# hub-i-proto-wireant01.net
KiCad netlist of a schematic drawn in EAGLE
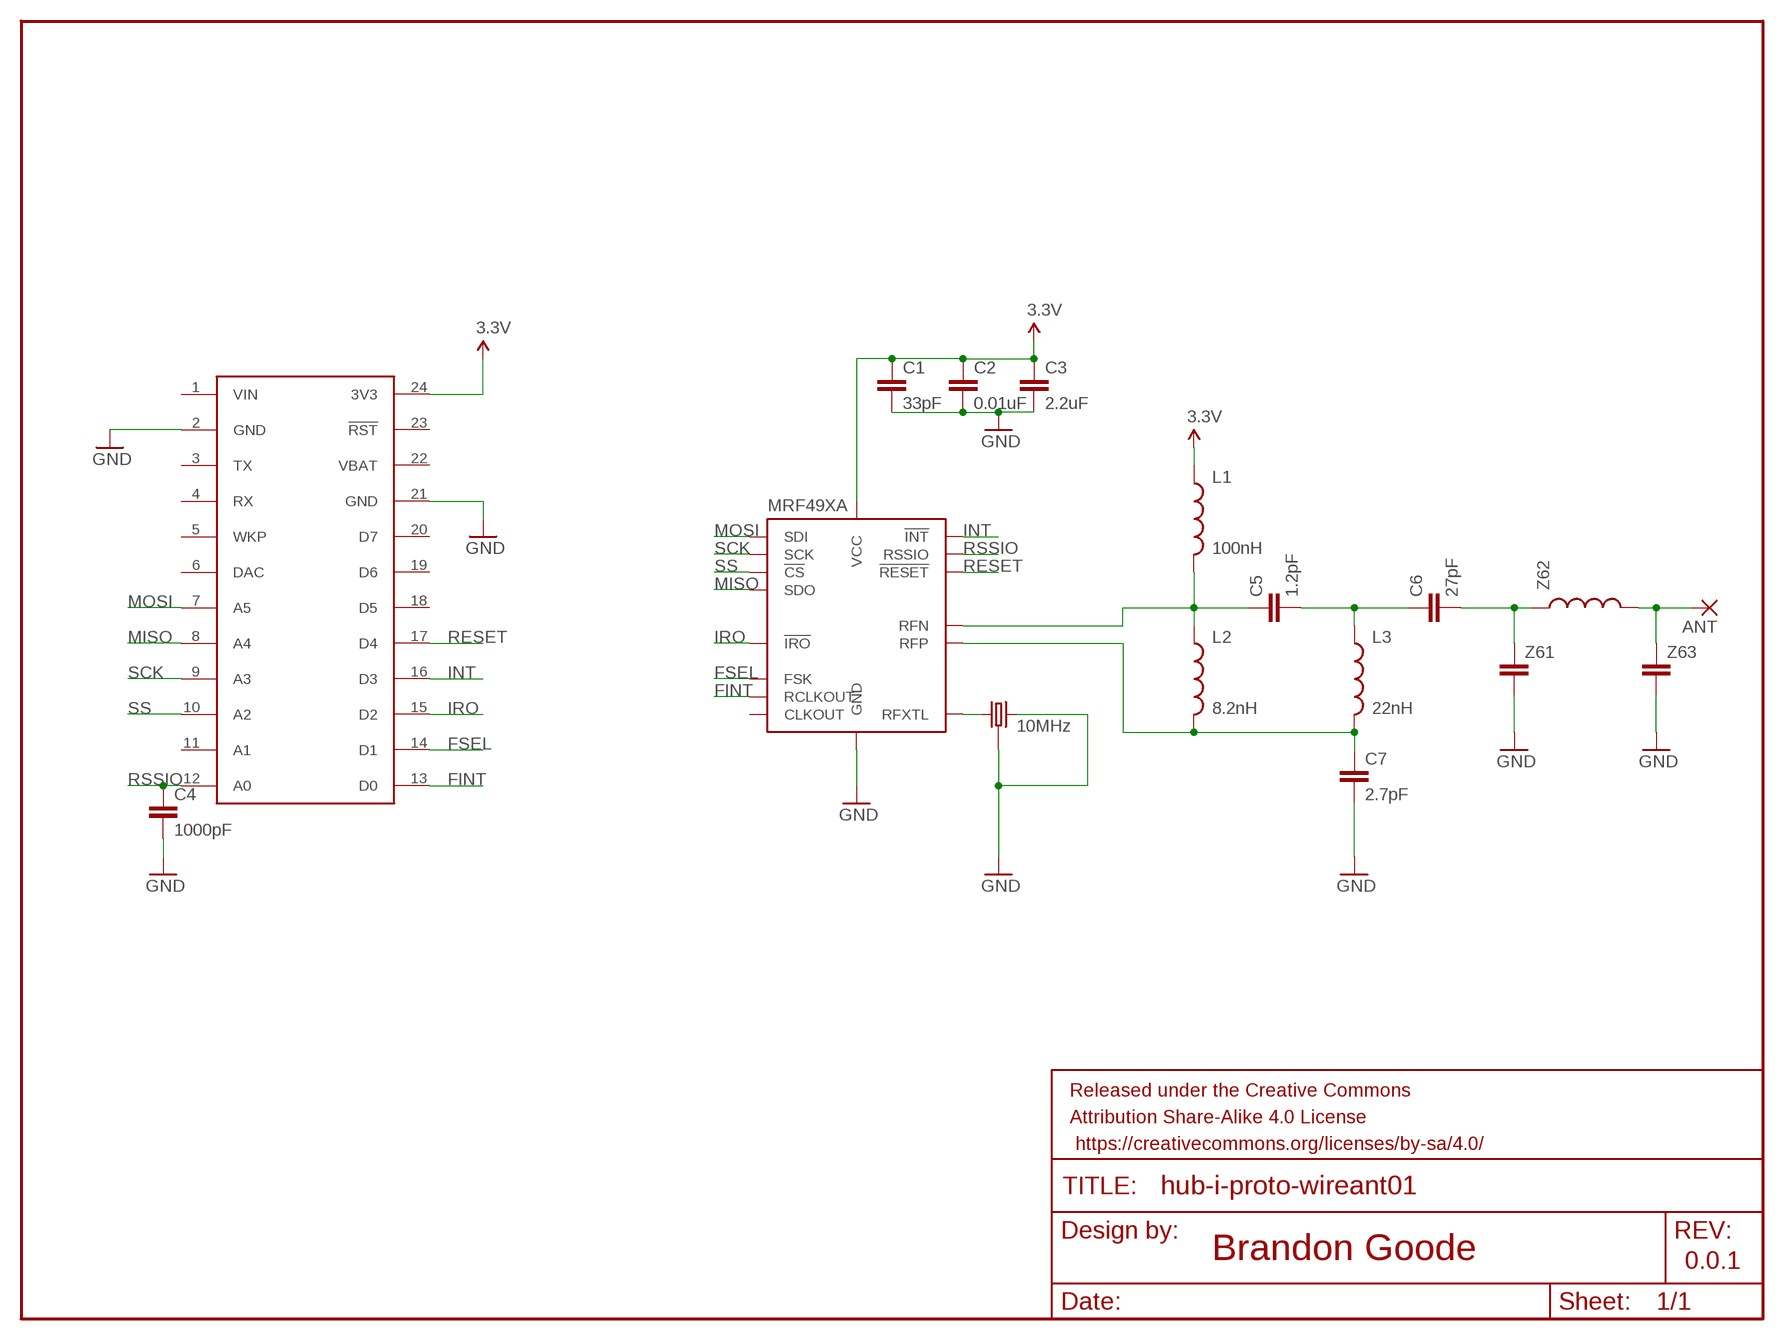
[diagram p0: schematic, sheet 1]

(export (version "E")
  (design (tool "Eeschema 10.0.6"))
  (components
    (comp (ref "ANT")
      (value "WIREPAD1,6/0,8")
      (footprint "eagle-import:1,6_0,8")
      (libsource (lib "eagle-import") (part "WIREPAD1,6/0,8"))
    )
    (comp (ref "C1")
      (value "33pF")
      (footprint "eagle-import:0603-CAP")
      (libsource (lib "eagle-import") (part "CAP0603-CAP"))
    )
    (comp (ref "C2")
      (value "0.01uF")
      (footprint "eagle-import:0603-CAP")
      (libsource (lib "eagle-import") (part "CAP0603-CAP"))
    )
    (comp (ref "C3")
      (value "2.2uF")
      (footprint "eagle-import:0603-CAP")
      (libsource (lib "eagle-import") (part "CAP0603-CAP"))
    )
    (comp (ref "C4")
      (value "1000pF")
      (footprint "eagle-import:0603-CAP")
      (libsource (lib "eagle-import") (part "CAP0603-CAP"))
    )
    (comp (ref "C5")
      (value "1.2pF")
      (footprint "eagle-import:0603-CAP")
      (libsource (lib "eagle-import") (part "CAP0603-CAP"))
    )
    (comp (ref "C6")
      (value "27pF")
      (footprint "eagle-import:0603-CAP")
      (libsource (lib "eagle-import") (part "CAP0603-CAP"))
    )
    (comp (ref "C7")
      (value "2.7pF")
      (footprint "eagle-import:0603-CAP")
      (libsource (lib "eagle-import") (part "CAP0603-CAP"))
    )
    (comp (ref "FRAME1")
      (value "FRAME-LETTER")
      (footprint "eagle-import:CREATIVE_COMMONS")
      (libsource (lib "eagle-import") (part "FRAME-LETTER"))
    )
    (comp (ref "L1")
      (value "100nH")
      (footprint "eagle-import:0603")
      (libsource (lib "eagle-import") (part "INDUCTOR0603"))
    )
    (comp (ref "L2")
      (value "8.2nH")
      (footprint "eagle-import:0603")
      (libsource (lib "eagle-import") (part "INDUCTOR0603"))
    )
    (comp (ref "L3")
      (value "22nH")
      (footprint "eagle-import:0603")
      (libsource (lib "eagle-import") (part "INDUCTOR0603"))
    )
    (comp (ref "MRF49XA")
      (value "MRF49XATSSOP")
      (footprint "eagle-import:TSSOP16")
      (libsource (lib "eagle-import") (part "MRF49XATSSOP"))
    )
    (comp (ref "SPARK")
      (value "SPARK_CORECORE")
      (footprint "eagle-import:SPARK_CORE")
      (libsource (lib "eagle-import") (part "SPARK_CORECORE"))
    )
    (comp (ref "Y1")
      (value "10MHz")
      (footprint "eagle-import:CRYSTAL-SMD-5X3")
      (libsource (lib "eagle-import") (part "CRYSTAL-GROUNDED"))
    )
    (comp (ref "Z61")
      (value "CAP0603-CAP")
      (footprint "eagle-import:0603-CAP")
      (libsource (lib "eagle-import") (part "CAP0603-CAP"))
    )
    (comp (ref "Z62")
      (value "INDUCTOR0603")
      (footprint "eagle-import:0603")
      (libsource (lib "eagle-import") (part "INDUCTOR0603"))
    )
    (comp (ref "Z63")
      (value "CAP0603-CAP")
      (footprint "eagle-import:0603-CAP")
      (libsource (lib "eagle-import") (part "CAP0603-CAP"))
    )
  )
  (nets
    (net (code "1") (name "/FINT") (class "Default")
      (node (ref "MRF49XA") (pin "7") (pinfunction "RCLKOUT_7") (pintype "bidirectional"))
      (node (ref "SPARK") (pin "13") (pinfunction "D0_13") (pintype "bidirectional"))
    )
    (net (code "2") (name "/FSEL") (class "Default")
      (node (ref "MRF49XA") (pin "6") (pinfunction "FSK_6") (pintype "bidirectional"))
      (node (ref "SPARK") (pin "14") (pinfunction "D1_14") (pintype "bidirectional"))
    )
    (net (code "3") (name "/INT") (class "Default")
      (node (ref "MRF49XA") (pin "16") (pinfunction "~{INT}_16") (pintype "bidirectional"))
      (node (ref "SPARK") (pin "16") (pinfunction "D3_16") (pintype "bidirectional"))
    )
    (net (code "4") (name "/IRO") (class "Default")
      (node (ref "MRF49XA") (pin "5") (pinfunction "~{IRO}_5") (pintype "output"))
      (node (ref "SPARK") (pin "15") (pinfunction "D2_15") (pintype "bidirectional"))
    )
    (net (code "5") (name "/MISO") (class "Default")
      (node (ref "MRF49XA") (pin "4") (pinfunction "SDO_4") (pintype "output"))
      (node (ref "SPARK") (pin "8") (pinfunction "A4_8") (pintype "bidirectional"))
    )
    (net (code "6") (name "/MOSI") (class "Default")
      (node (ref "MRF49XA") (pin "1") (pinfunction "SDI_1") (pintype "input"))
      (node (ref "SPARK") (pin "7") (pinfunction "A5_7") (pintype "bidirectional"))
    )
    (net (code "7") (name "/RESET") (class "Default")
      (node (ref "MRF49XA") (pin "10") (pinfunction "~{RESET}_10") (pintype "bidirectional"))
      (node (ref "SPARK") (pin "17") (pinfunction "D4_17") (pintype "bidirectional"))
    )
    (net (code "8") (name "/RSSIO") (class "Default")
      (node (ref "C4") (pin "1") (pinfunction "1_1") (pintype "passive"))
      (node (ref "MRF49XA") (pin "15") (pinfunction "RSSIO_15") (pintype "bidirectional"))
      (node (ref "SPARK") (pin "12") (pinfunction "A0_12") (pintype "bidirectional"))
    )
    (net (code "9") (name "/SCK") (class "Default")
      (node (ref "MRF49XA") (pin "2") (pinfunction "SCK_2") (pintype "input"))
      (node (ref "SPARK") (pin "9") (pinfunction "A3_9") (pintype "bidirectional"))
    )
    (net (code "10") (name "/SS") (class "Default")
      (node (ref "MRF49XA") (pin "3") (pinfunction "~{CS}_3") (pintype "input"))
      (node (ref "SPARK") (pin "10") (pinfunction "A2_10") (pintype "bidirectional"))
    )
    (net (code "11") (name "/VBAT") (class "Default")
      (node (ref "SPARK") (pin "22") (pinfunction "VBAT_22") (pintype "power_in"))
    )
    (net (code "12") (name "/VIN") (class "Default")
      (node (ref "SPARK") (pin "1") (pinfunction "VIN_1") (pintype "power_in"))
    )
    (net (code "13") (name "3.3V") (class "Default")
      (node (ref "C1") (pin "1") (pinfunction "1_1") (pintype "passive"))
      (node (ref "C2") (pin "1") (pinfunction "1_1") (pintype "passive"))
      (node (ref "C3") (pin "1") (pinfunction "1_1") (pintype "passive"))
      (node (ref "L1") (pin "1") (pinfunction "1_1") (pintype "passive"))
      (node (ref "MRF49XA") (pin "14") (pinfunction "VCC_14") (pintype "power_in"))
      (node (ref "SPARK") (pin "24") (pinfunction "3V3_24") (pintype "power_in"))
    )
    (net (code "14") (name "GND") (class "Default")
      (node (ref "C1") (pin "2") (pinfunction "2_2") (pintype "passive"))
      (node (ref "C2") (pin "2") (pinfunction "2_2") (pintype "passive"))
      (node (ref "C3") (pin "2") (pinfunction "2_2") (pintype "passive"))
      (node (ref "C4") (pin "2") (pinfunction "2_2") (pintype "passive"))
      (node (ref "C7") (pin "2") (pinfunction "2_2") (pintype "passive"))
      (node (ref "MRF49XA") (pin "11") (pinfunction "GND_11") (pintype "power_in"))
      (node (ref "SPARK") (pin "2") (pinfunction "GND_2") (pintype "power_in"))
      (node (ref "SPARK") (pin "21") (pinfunction "GND_21") (pintype "power_in"))
      (node (ref "Y1") (pin "1") (pinfunction "2_1") (pintype "passive"))
      (node (ref "Y1") (pin "2") (pinfunction "3_2") (pintype "passive"))
      (node (ref "Y1") (pin "4") (pinfunction "3_4") (pintype "passive"))
      (node (ref "Z61") (pin "2") (pinfunction "2_2") (pintype "passive"))
      (node (ref "Z63") (pin "2") (pinfunction "2_2") (pintype "passive"))
    )
    (net (code "15") (name "Net-(ANT-P)") (class "Default")
      (node (ref "ANT") (pin "1") (pinfunction "P_1") (pintype "passive"))
      (node (ref "Z62") (pin "2") (pinfunction "2_2") (pintype "passive"))
      (node (ref "Z63") (pin "1") (pinfunction "1_1") (pintype "passive"))
    )
    (net (code "16") (name "Net-(C5-Pad2)") (class "Default")
      (node (ref "C5") (pin "2") (pinfunction "2_2") (pintype "passive"))
      (node (ref "C6") (pin "1") (pinfunction "1_1") (pintype "passive"))
      (node (ref "L3") (pin "1") (pinfunction "1_1") (pintype "passive"))
    )
    (net (code "17") (name "Net-(C6-Pad2)") (class "Default")
      (node (ref "C6") (pin "2") (pinfunction "2_2") (pintype "passive"))
      (node (ref "Z61") (pin "1") (pinfunction "1_1") (pintype "passive"))
      (node (ref "Z62") (pin "1") (pinfunction "1_1") (pintype "passive"))
    )
    (net (code "18") (name "Net-(MRF49XA-RFN)") (class "Default")
      (node (ref "C5") (pin "1") (pinfunction "1_1") (pintype "passive"))
      (node (ref "L1") (pin "2") (pinfunction "2_2") (pintype "passive"))
      (node (ref "L2") (pin "1") (pinfunction "1_1") (pintype "passive"))
      (node (ref "MRF49XA") (pin "13") (pinfunction "RFN_13") (pintype "bidirectional"))
    )
    (net (code "19") (name "Net-(MRF49XA-RFP)") (class "Default")
      (node (ref "C7") (pin "1") (pinfunction "1_1") (pintype "passive"))
      (node (ref "L2") (pin "2") (pinfunction "2_2") (pintype "passive"))
      (node (ref "L3") (pin "2") (pinfunction "2_2") (pintype "passive"))
      (node (ref "MRF49XA") (pin "12") (pinfunction "RFP_12") (pintype "bidirectional"))
    )
    (net (code "20") (name "Net-(MRF49XA-RFXTL)") (class "Default")
      (node (ref "MRF49XA") (pin "9") (pinfunction "RFXTL_9") (pintype "input"))
      (node (ref "Y1") (pin "3") (pinfunction "1_3") (pintype "passive"))
    )
    (net (code "21") (name "unconnected-(MRF49XA-CLKOUT-Pad8)") (class "Default")
      (node (ref "MRF49XA") (pin "8") (pinfunction "CLKOUT_8") (pintype "output"))
    )
    (net (code "22") (name "unconnected-(SPARK-A1-Pad11)") (class "Default")
      (node (ref "SPARK") (pin "11") (pinfunction "A1_11") (pintype "bidirectional"))
    )
    (net (code "23") (name "unconnected-(SPARK-D5-Pad18)") (class "Default")
      (node (ref "SPARK") (pin "18") (pinfunction "D5_18") (pintype "bidirectional"))
    )
    (net (code "24") (name "unconnected-(SPARK-D6-Pad19)") (class "Default")
      (node (ref "SPARK") (pin "19") (pinfunction "D6_19") (pintype "bidirectional"))
    )
    (net (code "25") (name "unconnected-(SPARK-D7-Pad20)") (class "Default")
      (node (ref "SPARK") (pin "20") (pinfunction "D7_20") (pintype "bidirectional"))
    )
    (net (code "26") (name "unconnected-(SPARK-DAC-Pad6)") (class "Default")
      (node (ref "SPARK") (pin "6") (pinfunction "DAC_6") (pintype "bidirectional"))
    )
    (net (code "27") (name "unconnected-(SPARK-RX-Pad4)") (class "Default")
      (node (ref "SPARK") (pin "4") (pinfunction "RX_4") (pintype "bidirectional"))
    )
    (net (code "28") (name "unconnected-(SPARK-TX-Pad3)") (class "Default")
      (node (ref "SPARK") (pin "3") (pinfunction "TX_3") (pintype "bidirectional"))
    )
    (net (code "29") (name "unconnected-(SPARK-WKP-Pad5)") (class "Default")
      (node (ref "SPARK") (pin "5") (pinfunction "WKP_5") (pintype "bidirectional"))
    )
    (net (code "30") (name "unconnected-(SPARK-~{RST}-Pad23)") (class "Default")
      (node (ref "SPARK") (pin "23") (pinfunction "~{RST}_23") (pintype "bidirectional"))
    )
  )
)
